# EHDMIFPC01.net
KiCad netlist of a schematic drawn in EAGLE
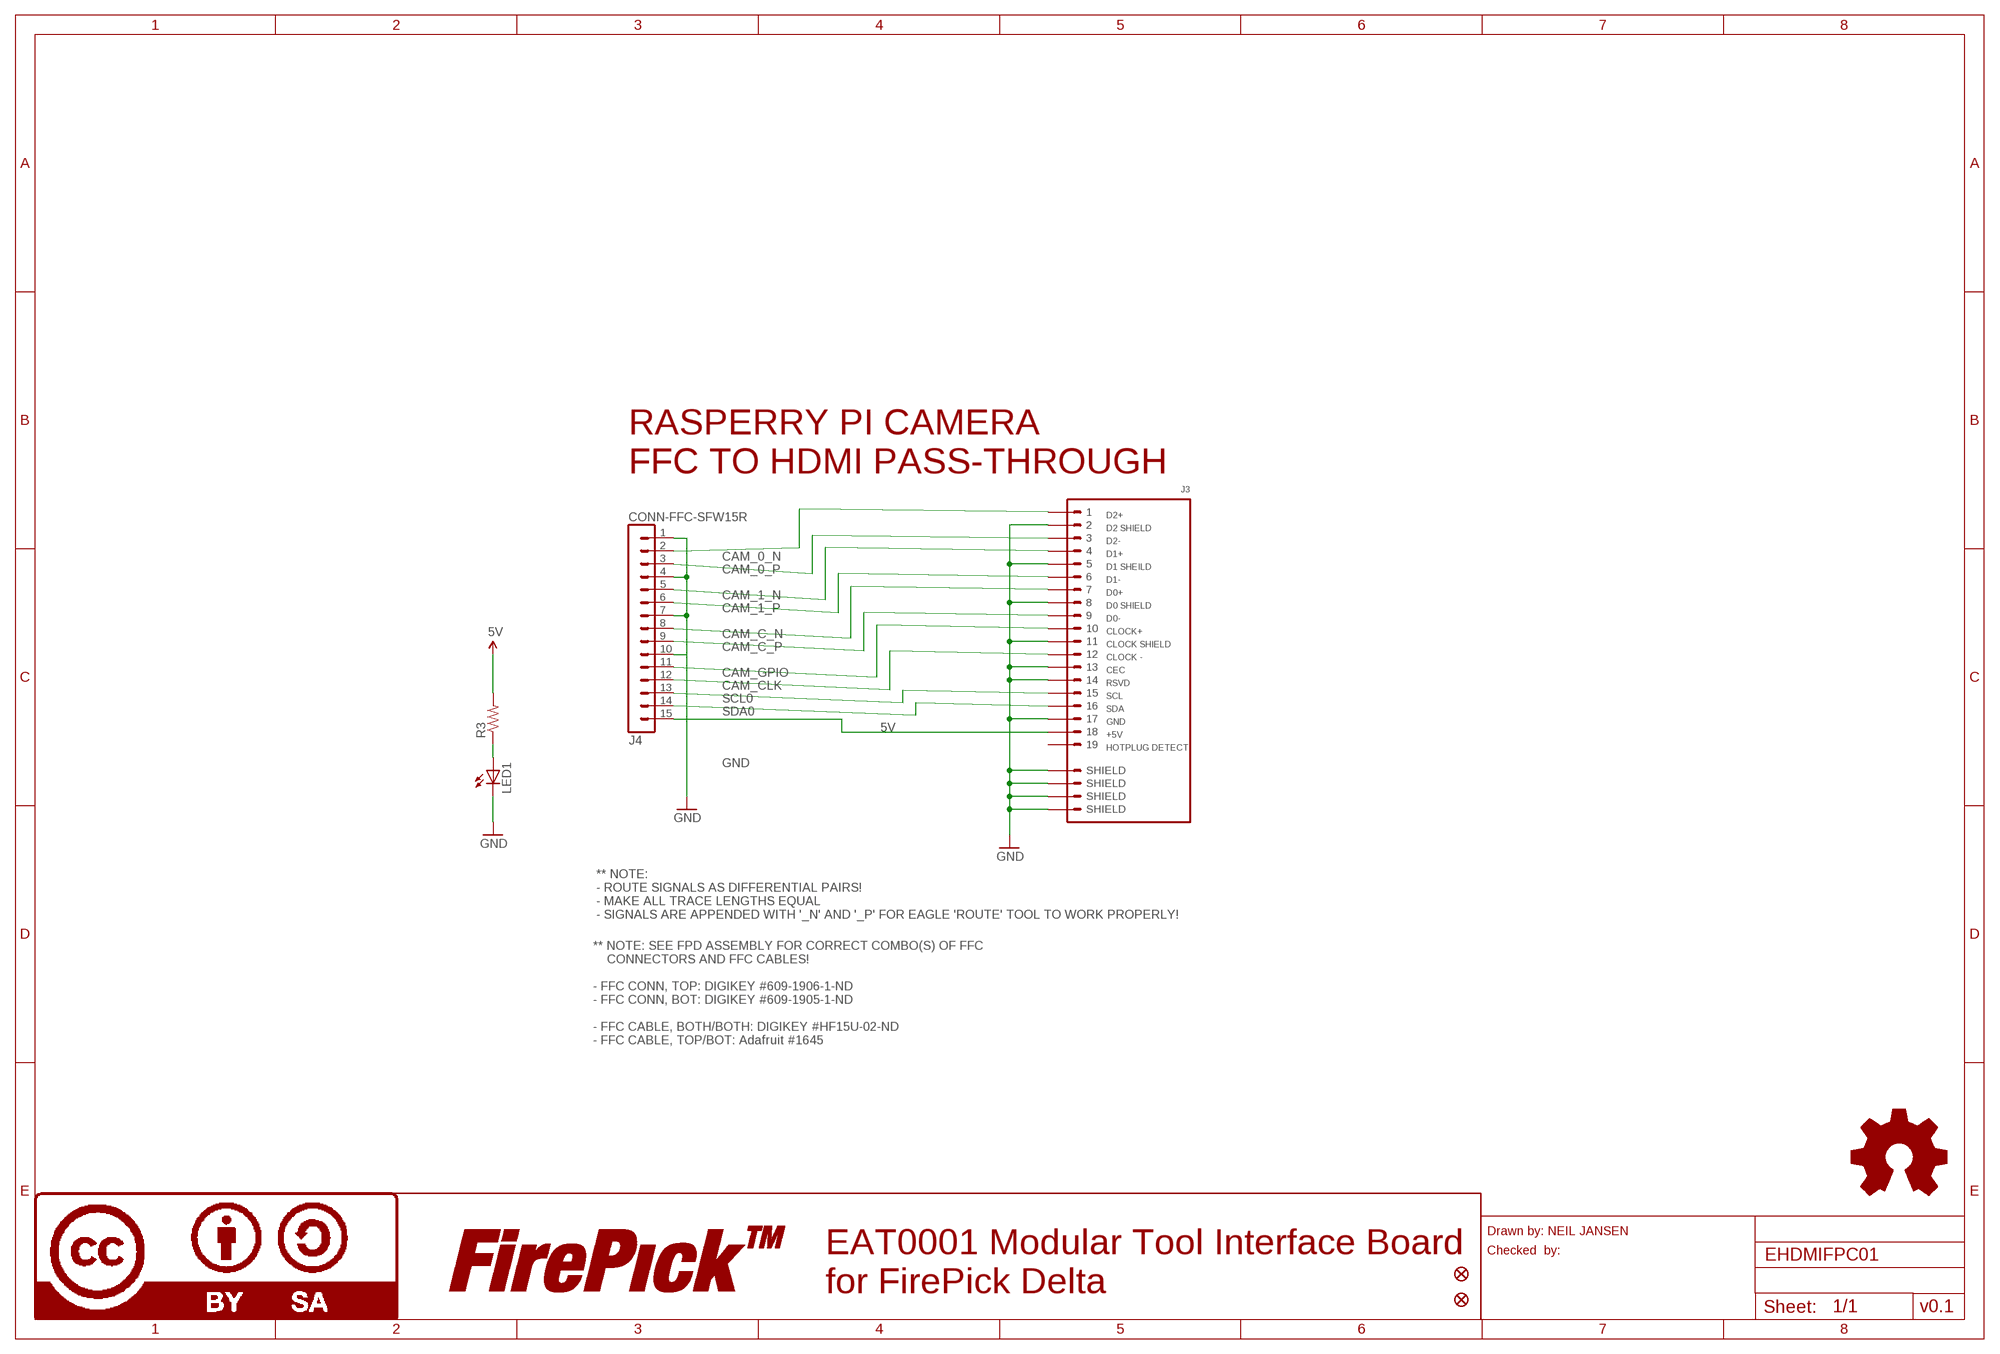
[diagram p0: schematic, sheet 1]

(export (version "E")
  (design (tool "Eeschema 10.0.6"))
  (components
    (comp (ref "FID3")
      (value "FIDUCIAL1X2")
      (footprint "eagle-import:FIDUCIAL-1X2")
      (libsource (lib "eagle-import") (part "FIDUCIAL1X2"))
    )
    (comp (ref "FID4")
      (value "FIDUCIAL1X2")
      (footprint "eagle-import:FIDUCIAL-1X2")
      (libsource (lib "eagle-import") (part "FIDUCIAL1X2"))
    )
    (comp (ref "J3")
      (value "CONN-HDMI")
      (footprint "eagle-import:CON-HDMI-FCI-10029449-001RLF")
      (libsource (lib "eagle-import") (part "CONN-HDMI"))
    )
    (comp (ref "J4")
      (value "CONN-FFC-SFW15R")
      (footprint "eagle-import:CON-FFC-SFW15R")
      (libsource (lib "eagle-import") (part "CONN-FFC-SFW15R"))
    )
    (comp (ref "LED1")
      (value "LED1206")
      (footprint "eagle-import:LED-1206")
      (libsource (lib "eagle-import") (part "LED1206"))
    )
    (comp (ref "LOGO4")
      (value "LOGO-FIREPICKMEDIUM")
      (footprint "eagle-import:LOGO-FIREPICK-MEDIUM")
      (libsource (lib "eagle-import") (part "LOGO-FIREPICKMEDIUM"))
    )
    (comp (ref "LOGO5")
      (value "LOGO-OSHWSMALL")
      (footprint "eagle-import:LOGO-OSHW-SMALL")
      (libsource (lib "eagle-import") (part "LOGO-OSHWSMALL"))
    )
    (comp (ref "LOGO6")
      (value "LOGO-CC-BY-SAMEDIUM")
      (footprint "eagle-import:LOGO-CC-BY-SA-MEDIUM")
      (libsource (lib "eagle-import") (part "LOGO-CC-BY-SAMEDIUM"))
    )
    (comp (ref "R3")
      (value "RESISTOR0805-RES")
      (footprint "eagle-import:0805")
      (libsource (lib "eagle-import") (part "RESISTOR0805-RES"))
    )
  )
  (nets
    (net (code "1") (name "/CAM_0_N") (class "Default")
      (node (ref "J3") (pin "1") (pinfunction "1_1") (pintype "passive"))
      (node (ref "J4") (pin "2") (pinfunction "2_2") (pintype "passive"))
    )
    (net (code "2") (name "/CAM_0_P") (class "Default")
      (node (ref "J3") (pin "3") (pinfunction "3_3") (pintype "passive"))
      (node (ref "J4") (pin "3") (pinfunction "3_3") (pintype "passive"))
    )
    (net (code "3") (name "/CAM_1_N") (class "Default")
      (node (ref "J3") (pin "4") (pinfunction "4_4") (pintype "passive"))
      (node (ref "J4") (pin "5") (pinfunction "5_5") (pintype "passive"))
    )
    (net (code "4") (name "/CAM_1_P") (class "Default")
      (node (ref "J3") (pin "6") (pinfunction "6_6") (pintype "passive"))
      (node (ref "J4") (pin "6") (pinfunction "6_6") (pintype "passive"))
    )
    (net (code "5") (name "/CAM_C_N") (class "Default")
      (node (ref "J3") (pin "7") (pinfunction "7_7") (pintype "passive"))
      (node (ref "J4") (pin "8") (pinfunction "8_8") (pintype "passive"))
    )
    (net (code "6") (name "/CAM_C_P") (class "Default")
      (node (ref "J3") (pin "9") (pinfunction "9_9") (pintype "passive"))
      (node (ref "J4") (pin "9") (pinfunction "9_9") (pintype "passive"))
    )
    (net (code "7") (name "5V") (class "Default")
      (node (ref "J3") (pin "18") (pinfunction "18_18") (pintype "passive"))
      (node (ref "J4") (pin "15") (pinfunction "15_15") (pintype "passive"))
      (node (ref "R3") (pin "2") (pinfunction "2_2") (pintype "passive"))
    )
    (net (code "8") (name "GND") (class "Default")
      (node (ref "J3") (pin "11") (pinfunction "11_11") (pintype "passive"))
      (node (ref "J3") (pin "13") (pinfunction "13_13") (pintype "passive"))
      (node (ref "J3") (pin "14") (pinfunction "14_14") (pintype "passive"))
      (node (ref "J3") (pin "17") (pinfunction "17_17") (pintype "passive"))
      (node (ref "J3") (pin "2") (pinfunction "2_2") (pintype "passive"))
      (node (ref "J3") (pin "5") (pinfunction "5_5") (pintype "passive"))
      (node (ref "J3") (pin "8") (pinfunction "8_8") (pintype "passive"))
      (node (ref "J3") (pin "SHIELD1") (pinfunction "SHIELD_SHIELD1") (pintype "passive"))
      (node (ref "J3") (pin "SHIELD2") (pinfunction "SHIELD_SHIELD2") (pintype "passive"))
      (node (ref "J3") (pin "SHIELD3") (pinfunction "SHIELD_SHIELD3") (pintype "passive"))
      (node (ref "J3") (pin "SHIELD4") (pinfunction "SHIELD_SHIELD4") (pintype "passive"))
      (node (ref "J4") (pin "1") (pinfunction "1_1") (pintype "passive"))
      (node (ref "J4") (pin "10") (pinfunction "10_10") (pintype "passive"))
      (node (ref "J4") (pin "4") (pinfunction "4_4") (pintype "passive"))
      (node (ref "J4") (pin "7") (pinfunction "7_7") (pintype "passive"))
      (node (ref "LED1") (pin "C") (pinfunction "C_C") (pintype "passive"))
    )
    (net (code "9") (name "Net-(J3-Pad10)") (class "Default")
      (node (ref "J3") (pin "10") (pinfunction "10_10") (pintype "passive"))
      (node (ref "J4") (pin "11") (pinfunction "11_11") (pintype "passive"))
    )
    (net (code "10") (name "Net-(J3-Pad12)") (class "Default")
      (node (ref "J3") (pin "12") (pinfunction "12_12") (pintype "passive"))
      (node (ref "J4") (pin "12") (pinfunction "12_12") (pintype "passive"))
    )
    (net (code "11") (name "Net-(J3-Pad15)") (class "Default")
      (node (ref "J3") (pin "15") (pinfunction "15_15") (pintype "passive"))
      (node (ref "J4") (pin "13") (pinfunction "13_13") (pintype "passive"))
    )
    (net (code "12") (name "Net-(J3-Pad16)") (class "Default")
      (node (ref "J3") (pin "16") (pinfunction "16_16") (pintype "passive"))
      (node (ref "J4") (pin "14") (pinfunction "14_14") (pintype "passive"))
    )
    (net (code "13") (name "Net-(LED1-PadA)") (class "Default")
      (node (ref "LED1") (pin "A") (pinfunction "A_A") (pintype "passive"))
      (node (ref "R3") (pin "1") (pinfunction "1_1") (pintype "passive"))
    )
    (net (code "14") (name "unconnected-(J3-Pad19)") (class "Default")
      (node (ref "J3") (pin "19") (pinfunction "19_19") (pintype "passive"))
    )
  )
)
